# led.net
KiCad netlist of a schematic drawn in EAGLE
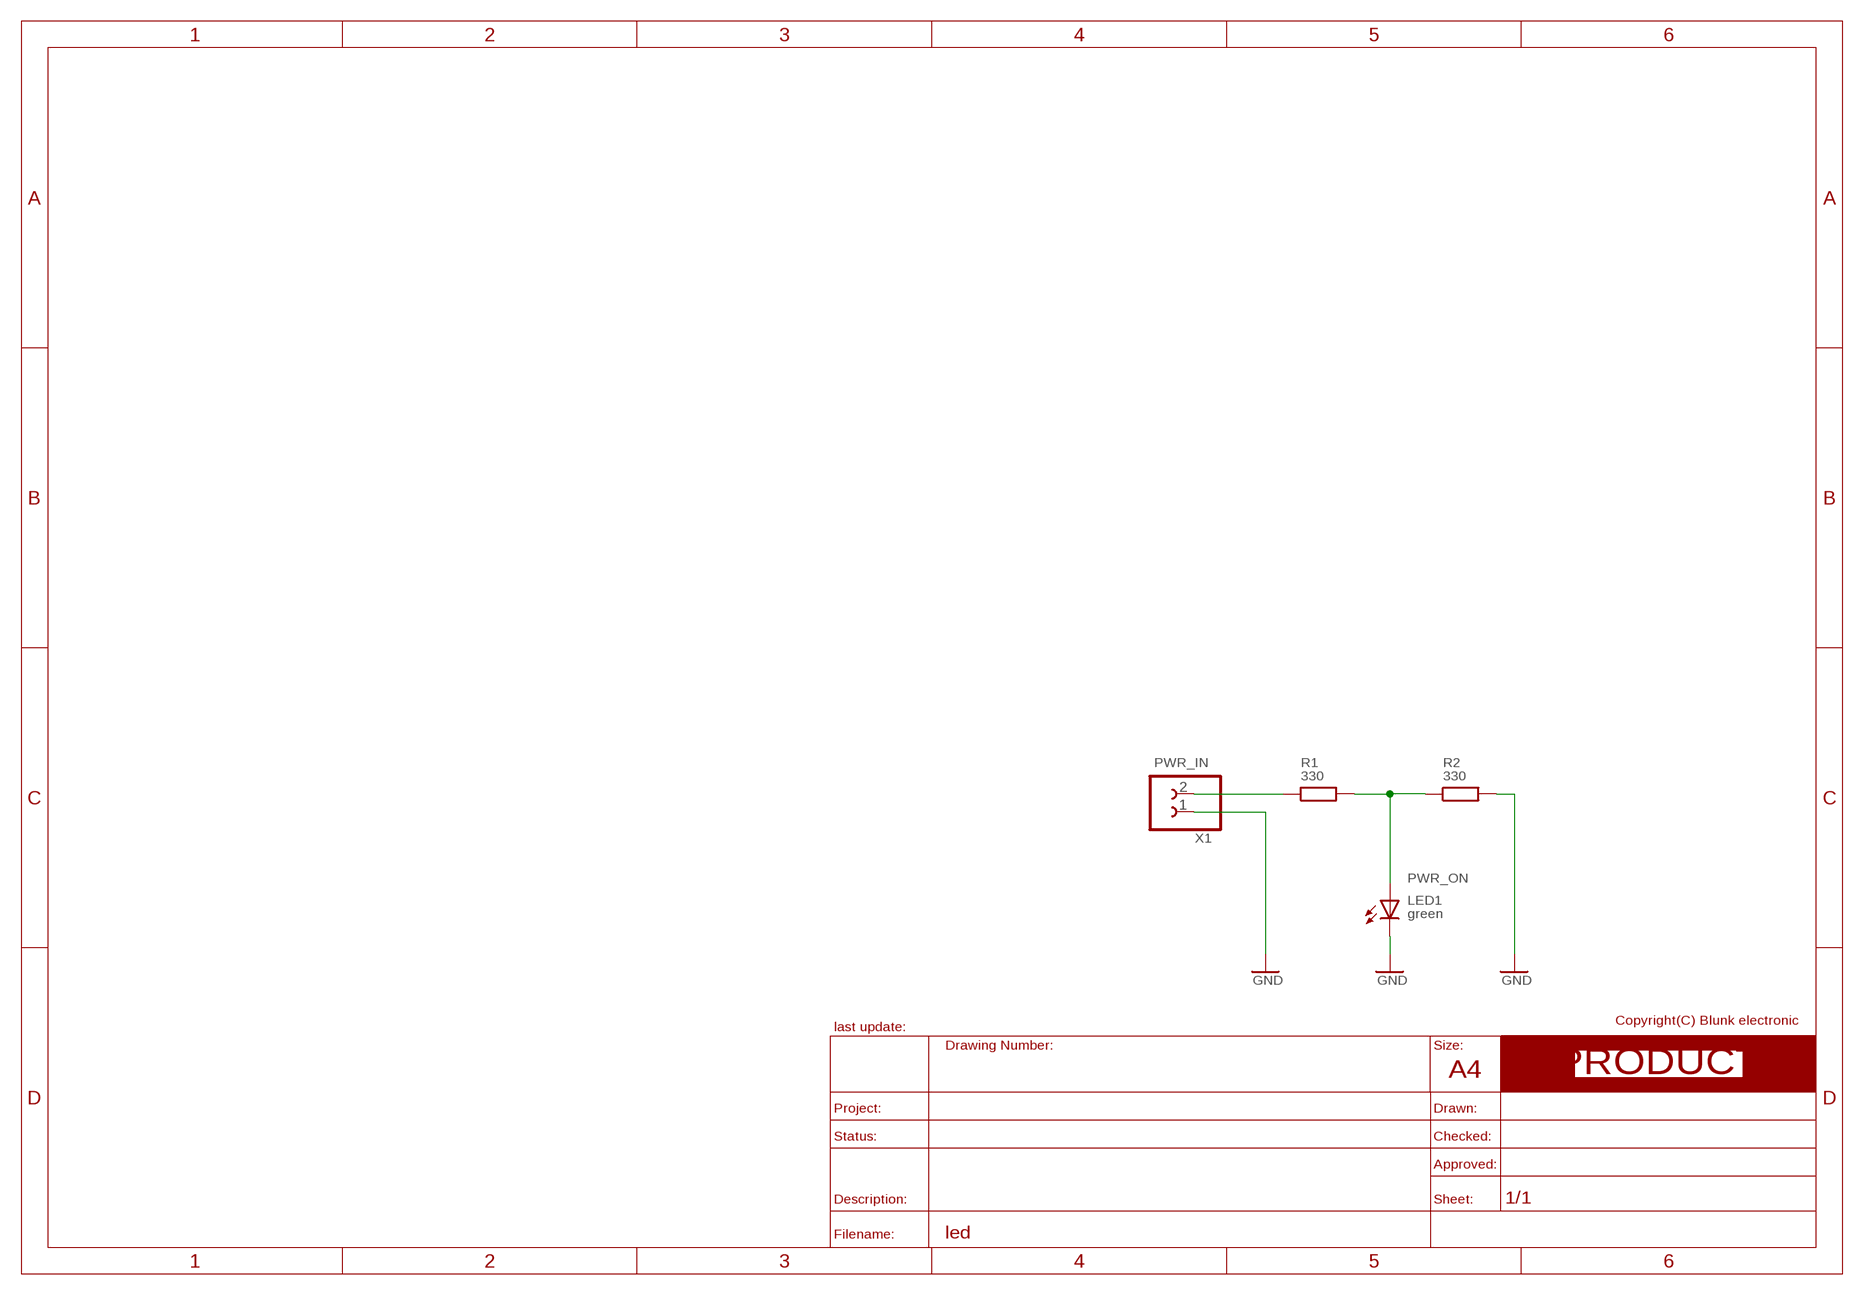
[diagram p0: schematic, sheet 1]

(export (version "E")
  (design (tool "Eeschema 10.0.6"))
  (components
    (comp (ref "LED1")
      (value "green")
      (footprint "eagle-import:S_0805")
      (fields (field (name "FUNCTION") "PWR_ON") (field (name "PART_CODE_BEL") "LED_PAC_S_0805_VAL_green"))
      (libsource (lib "eagle-import") (part "LED_S_0805"))
    )
    (comp (ref "R1")
      (value "330")
      (footprint "eagle-import:S_0805")
      (fields (field (name "PART_CODE_BEL") "R_PAC_S_0805_VAL_330"))
      (libsource (lib "eagle-import") (part "R_S_0805"))
    )
    (comp (ref "R2")
      (value "330")
      (footprint "eagle-import:S_0805")
      (fields (field (name "PART_CODE_BEL") "R_PAC_S_0805_VAL_330"))
      (libsource (lib "eagle-import") (part "R_S_0805"))
    )
    (comp (ref "X1")
      (value "CLAMP_1X2-T-2.5MM")
      (footprint "eagle-import:T_WIRE_CLAMP_1X2_PITCH_2MM5")
      (fields (field (name "FUNCTION") "PWR_IN"))
      (libsource (lib "eagle-import") (part "CLAMP_1X2-T-2.5MM"))
    )
  )
  (nets
    (net (code "1") (name "GND") (class "Default")
      (node (ref "LED1") (pin "C") (pinfunction "C_C") (pintype "passive"))
      (node (ref "R2") (pin "2") (pinfunction "2_2") (pintype "passive"))
      (node (ref "X1") (pin "1") (pinfunction "1_1") (pintype "passive"))
    )
    (net (code "2") (name "Net-(LED1-PadA)") (class "Default")
      (node (ref "LED1") (pin "A") (pinfunction "A_A") (pintype "passive"))
      (node (ref "R1") (pin "2") (pinfunction "2_2") (pintype "passive"))
      (node (ref "R2") (pin "1") (pinfunction "1_1") (pintype "passive"))
    )
    (net (code "3") (name "Net-(R1-Pad1)") (class "Default")
      (node (ref "R1") (pin "1") (pinfunction "1_1") (pintype "passive"))
      (node (ref "X1") (pin "2") (pinfunction "2_2") (pintype "passive"))
    )
  )
)
